# Brduino-MCU-Main.net
KiCad netlist of a schematic drawn in Altium Designer
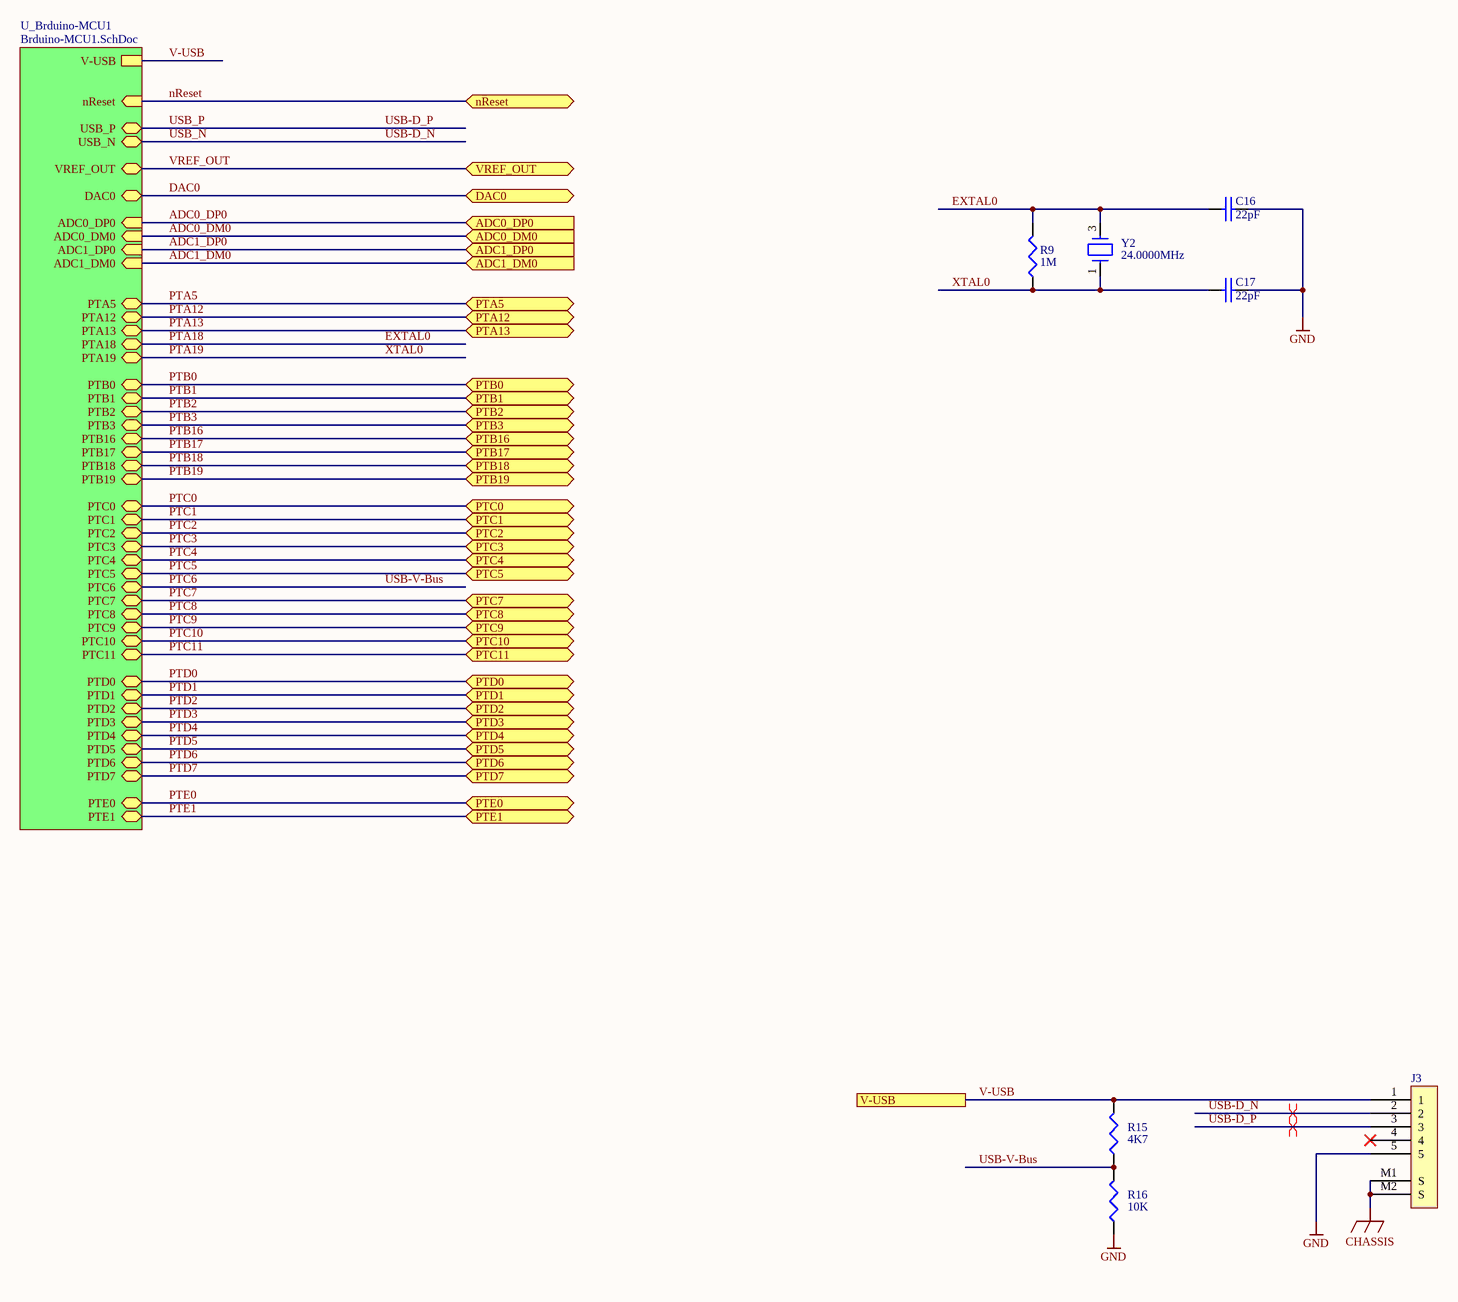
[diagram p0: Brduino-MCU-Main.SchDoc]

(export (version "E")
  (design (tool "Eeschema 10.0.6"))
  (components
    (comp (ref "C16")
      (value "22pF")
      (footprint "C0402")
      (description "CAP CER 22PF 16V C0G/NP0 0402")
      (fields (field (name "Comment") "C"))
      (libsource (lib "Brduino-Nano") (part "CAP"))
    )
    (comp (ref "C17")
      (value "22pF")
      (footprint "C0402")
      (description "CAP CER 22PF 16V C0G/NP0 0402")
      (fields (field (name "Comment") "C"))
      (libsource (lib "Brduino-Nano") (part "CAP"))
    )
    (comp (ref "J3")
      (value "X")
      (footprint "Molex-0565790519")
      (description "CONN RCPT USB2.0 MINI AB 5P R/A")
      (libsource (lib "Brduino-Nano") (part "MICRO-USB"))
    )
    (comp (ref "R9")
      (value "1M")
      (footprint "R0402")
      (description "RES SMD 1M OHM 1% 1/16W 0402")
      (fields (field (name "Comment") "R"))
      (libsource (lib "Brduino-Nano") (part "RES1A"))
    )
    (comp (ref "R15")
      (value "4K7")
      (footprint "R0402")
      (description "RES SMD 4.7K OHM 1% 1/16W 0402")
      (fields (field (name "Comment") "R"))
      (libsource (lib "Brduino-Nano") (part "RES1A"))
    )
    (comp (ref "R16")
      (value "10K")
      (footprint "R0402")
      (description "RES SMD 10K OHM 1% 1/16W 0402")
      (fields (field (name "Comment") "R"))
      (libsource (lib "Brduino-Nano") (part "RES1A"))
    )
    (comp (ref "Y2")
      (value "24.0000MHz")
      (footprint "FA-238")
      (description "CRYSTAL 24.0000MHZ 18PF SMD")
      (fields (field (name "Comment") "Y"))
      (libsource (lib "Brduino-Nano") (part "FA-238"))
    )
  )
  (nets
    (net (code "6") (name "/EXTAL0") (class "Default")
      (node (ref "C16") (pin "1") (pinfunction "1_1") (pintype "passive"))
      (node (ref "R9") (pin "2") (pinfunction "2_2") (pintype "passive"))
      (node (ref "Y2") (pin "3") (pinfunction "3_3") (pintype "passive"))
    )
    (net (code "10") (name "/PTA19") (class "Default")
      (node (ref "C17") (pin "1") (pinfunction "1_1") (pintype "passive"))
      (node (ref "R9") (pin "1") (pinfunction "1_1") (pintype "passive"))
      (node (ref "Y2") (pin "1") (pinfunction "1_1") (pintype "passive"))
    )
    (net (code "25") (name "/PTC6") (class "Default")
      (node (ref "R15") (pin "1") (pinfunction "1_1") (pintype "passive"))
      (node (ref "R16") (pin "2") (pinfunction "2_2") (pintype "passive"))
    )
    (net (code "41") (name "/USB-D_N") (class "Default")
      (node (ref "J3") (pin "2") (pinfunction "2_2") (pintype "passive"))
    )
    (net (code "42") (name "/USB-D_P") (class "Default")
      (node (ref "J3") (pin "3") (pinfunction "3_3") (pintype "passive"))
    )
    (net (code "43") (name "/V-USB") (class "Default")
      (node (ref "J3") (pin "1") (pinfunction "1_1") (pintype "passive"))
      (node (ref "R15") (pin "2") (pinfunction "2_2") (pintype "passive"))
    )
    (net (code "46") (name "CHASSIS") (class "Default")
      (node (ref "J3") (pin "M1") (pinfunction "S_M1") (pintype "passive"))
      (node (ref "J3") (pin "M2") (pinfunction "S_M2") (pintype "passive"))
    )
    (net (code "47") (name "GND") (class "Default")
      (node (ref "C16") (pin "2") (pinfunction "2_2") (pintype "passive"))
      (node (ref "C17") (pin "2") (pinfunction "2_2") (pintype "passive"))
      (node (ref "J3") (pin "5") (pinfunction "5_5") (pintype "passive"))
      (node (ref "R16") (pin "1") (pinfunction "1_1") (pintype "passive"))
    )
    (net (code "48") (name "unconnected-(J3-Pad4)") (class "Default")
      (node (ref "J3") (pin "4") (pinfunction "4_4") (pintype "passive+no_connect"))
    )
  )
)
